# 2-MCU.net
KiCad netlist of a schematic drawn in Altium Designer
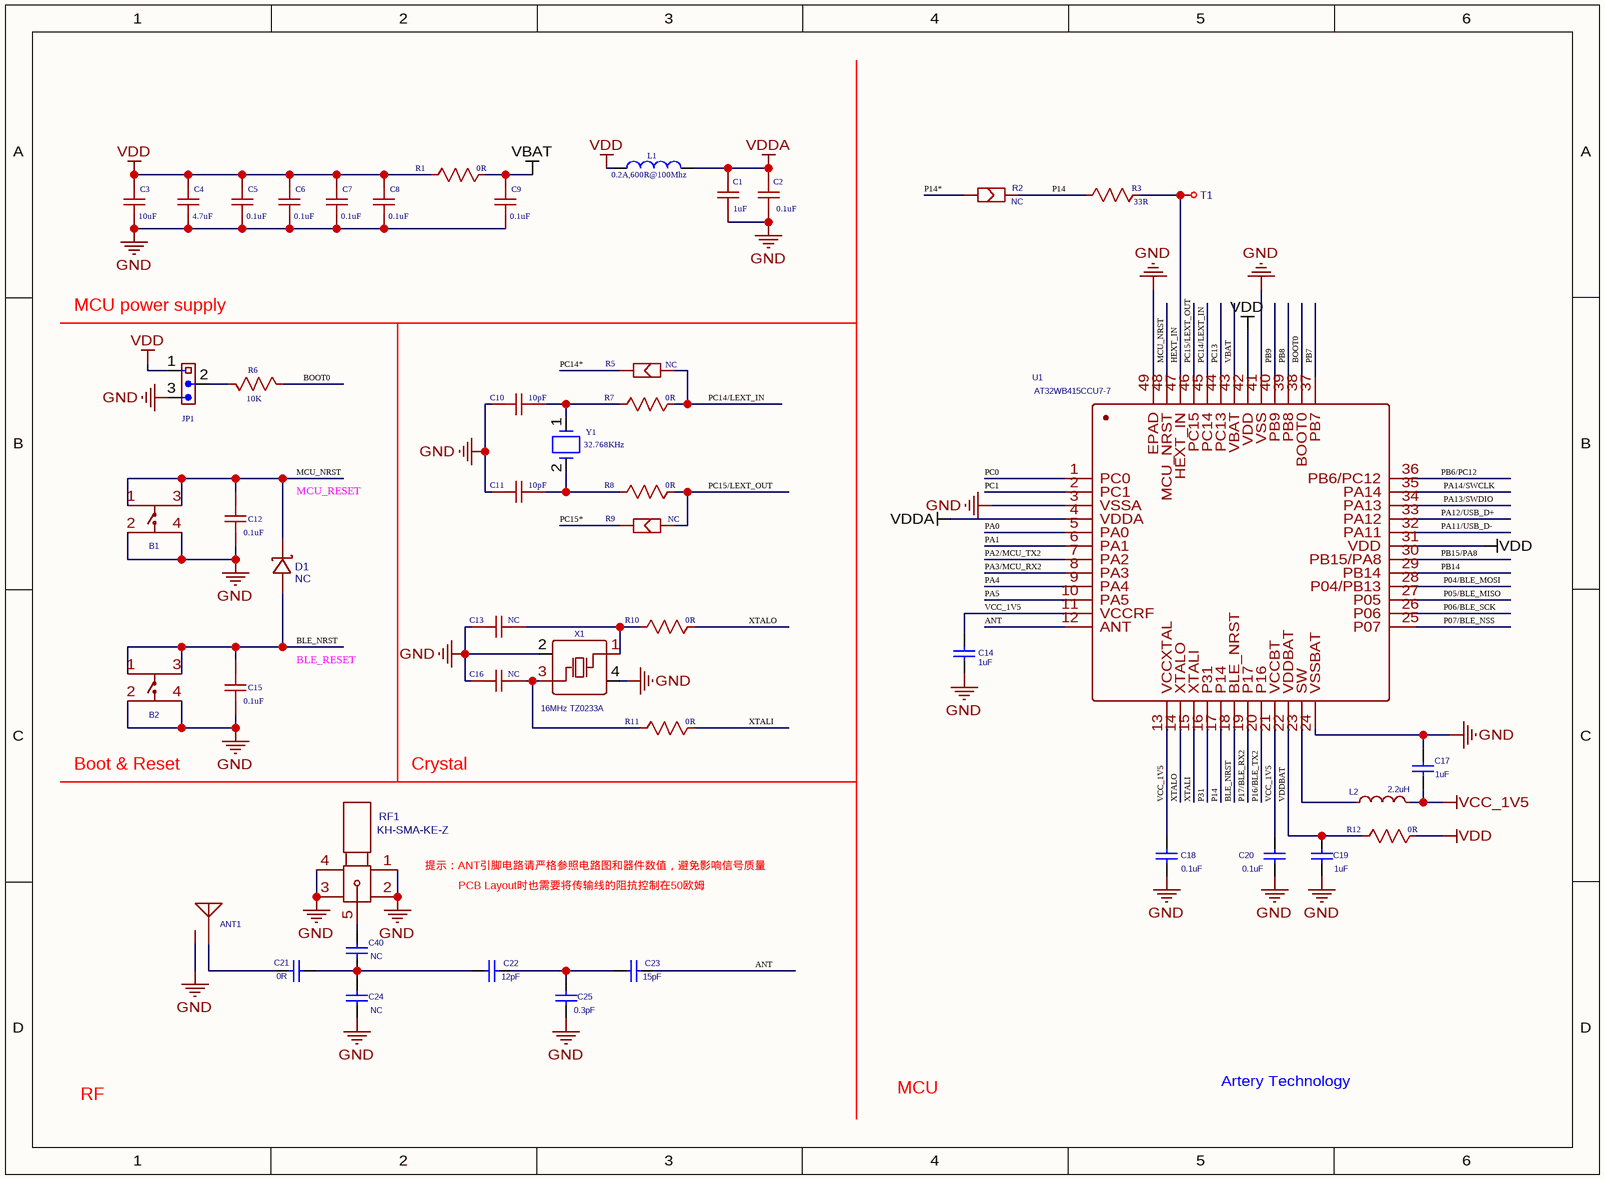
[diagram p0: 2-MCU.schdoc]

(export (version "E")
  (design (tool "Eeschema 10.0.6"))
  (components
    (comp (ref "ANT1")
      (value "AN2051-245")
      (fields (field (name "BOM_SUPPLIER PART") "C99727"))
      (libsource (lib "altium-import") (part "root_0_AN2051-245_"))
    )
    (comp (ref "B1")
      (value "贴片按键6*6*5 黑色")
      (fields
        (field (name "BOM_SUPPLIER PART") "C707347")
        (field (name "BOM_MANUFACTURER PART") "K2-1102SP-C3SC-04")
        (field (name "CONTRIBUTOR") "LCSC")
      )
      (libsource (lib "altium-import") (part "root_0_贴片按键6*6*5 黑色_"))
    )
    (comp (ref "B2")
      (value "贴片按键6*6*5 黑色")
      (fields
        (field (name "BOM_SUPPLIER PART") "C707347")
        (field (name "BOM_MANUFACTURER PART") "K2-1102SP-C3SC-04")
        (field (name "CONTRIBUTOR") "LCSC")
      )
      (libsource (lib "altium-import") (part "root_0_贴片按键6*6*5 黑色_"))
    )
    (comp (ref "C1")
      (value "1uF")
      (fields (field (name "CONTRIBUTOR") "LCEDA_Lib"))
      (libsource (lib "altium-import") (part "root_1_1uF_"))
    )
    (comp (ref "C2")
      (value "0.1uF")
      (fields (field (name "CONTRIBUTOR") "LCEDA_Lib"))
      (libsource (lib "altium-import") (part "root_1_0.1uF_"))
    )
    (comp (ref "C3")
      (value "10uF")
      (fields (field (name "CONTRIBUTOR") "LCEDA_Lib"))
      (libsource (lib "altium-import") (part "root_3_10uF_"))
    )
    (comp (ref "C4")
      (value "4.7uF")
      (fields (field (name "CONTRIBUTOR") "LCEDA_Lib"))
      (libsource (lib "altium-import") (part "root_3_4.7uF_"))
    )
    (comp (ref "C5")
      (value "0.1uF")
      (fields (field (name "CONTRIBUTOR") "LCEDA_Lib"))
      (libsource (lib "altium-import") (part "root_3_0.1uF_"))
    )
    (comp (ref "C6")
      (value "0.1uF")
      (fields (field (name "CONTRIBUTOR") "LCEDA_Lib"))
      (libsource (lib "altium-import") (part "root_3_0.1uF_"))
    )
    (comp (ref "C7")
      (value "0.1uF")
      (fields (field (name "CONTRIBUTOR") "LCEDA_Lib"))
      (libsource (lib "altium-import") (part "root_3_0.1uF_"))
    )
    (comp (ref "C8")
      (value "0.1uF")
      (fields (field (name "CONTRIBUTOR") "LCEDA_Lib"))
      (libsource (lib "altium-import") (part "root_3_0.1uF_"))
    )
    (comp (ref "C9")
      (value "0.1uF")
      (fields (field (name "CONTRIBUTOR") "LCEDA_Lib"))
      (libsource (lib "altium-import") (part "root_3_0.1uF_"))
    )
    (comp (ref "C10")
      (value "10pF")
      (fields (field (name "CONTRIBUTOR") "LCEDA_Lib"))
      (libsource (lib "altium-import") (part "root_0_10pF_"))
    )
    (comp (ref "C11")
      (value "10pF")
      (fields (field (name "CONTRIBUTOR") "LCEDA_Lib"))
      (libsource (lib "altium-import") (part "root_0_10pF_"))
    )
    (comp (ref "C12")
      (value "0.1uF")
      (fields (field (name "CONTRIBUTOR") "LCEDA_Lib"))
      (libsource (lib "altium-import") (part "root_1_0.1uF_"))
    )
    (comp (ref "C13")
      (value "NC")
      (fields (field (name "CONTRIBUTOR") "LCEDA_Lib"))
      (libsource (lib "altium-import") (part "root_0_NC_"))
    )
    (comp (ref "C14") (value "1uF") (libsource (lib "") (part "root_1_1uF__1")))
    (comp (ref "C15")
      (value "0.1uF")
      (fields (field (name "CONTRIBUTOR") "LCEDA_Lib"))
      (libsource (lib "altium-import") (part "root_1_0.1uF_"))
    )
    (comp (ref "C16")
      (value "NC")
      (fields (field (name "CONTRIBUTOR") "LCEDA_Lib"))
      (libsource (lib "altium-import") (part "root_0_NC_"))
    )
    (comp (ref "C17") (value "1uF") (libsource (lib "altium-import") (part "root_3_1uF_")))
    (comp (ref "C18") (value "0.1uF") (libsource (lib "") (part "root_3_0.1uF__1")))
    (comp (ref "C19") (value "1uF") (libsource (lib "altium-import") (part "root_3_1uF_")))
    (comp (ref "C20") (value "0.1uF") (libsource (lib "") (part "root_1_0.1uF__1")))
    (comp (ref "C21") (value "0R") (libsource (lib "altium-import") (part "root_0_0R_")))
    (comp (ref "C22") (value "12pF") (libsource (lib "altium-import") (part "root_2_12pF_")))
    (comp (ref "C23") (value "15pF") (libsource (lib "altium-import") (part "root_2_15pF_")))
    (comp (ref "C24") (value "NC") (libsource (lib "altium-import") (part "root_3_NC_")))
    (comp (ref "C25") (value "0.3pF") (libsource (lib "altium-import") (part "root_3_0.3pF_")))
    (comp (ref "C40") (value "NC") (libsource (lib "altium-import") (part "root_3_NC_")))
    (comp (ref "D1")
      (value "NC")
      (fields (field (name "BOM_MANUFACTURER PART") "B5819WS") (field (name "BOM_SUPPLIER PART") "C64886"))
      (libsource (lib "") (part "root_3_NC__1"))
    )
    (comp (ref "JP1") (value "Header 1x3") (libsource (lib "altium-import") (part "root_2_Header 1x3_")))
    (comp (ref "L1")
      (value "0.2A,600R@100Mhz")
      (fields (field (name "CONTRIBUTOR") "twb17"))
      (libsource (lib "altium-import") (part "root_0_0.2A,600R@100Mhz_"))
    )
    (comp (ref "L2")
      (value "2.2uH")
      (fields
        (field (name "BOM_MANUFACTURER PART") "MPH201210S2R2MT")
        (field (name "BOM_SUPPLIER PART") "C55755")
      )
      (libsource (lib "altium-import") (part "root_0_2.2uH_"))
    )
    (comp (ref "R1")
      (value "0R")
      (fields (field (name "CONTRIBUTOR") "LCEDA_Lib"))
      (libsource (lib "altium-import") (part "root_2_0R_"))
    )
    (comp (ref "R2")
      (value "NC")
      (fields (field (name "CONTRIBUTOR") "twb17"))
      (libsource (lib "") (part "root_0_NC__1"))
    )
    (comp (ref "R3")
      (value "33R")
      (fields (field (name "CONTRIBUTOR") "LCEDA_Lib"))
      (libsource (lib "altium-import") (part "root_2_33R_"))
    )
    (comp (ref "R5")
      (value "NC")
      (fields (field (name "CONTRIBUTOR") "twb17"))
      (libsource (lib "altium-import") (part "root_2_NC_"))
    )
    (comp (ref "R6")
      (value "10K")
      (fields (field (name "CONTRIBUTOR") "LCEDA_Lib"))
      (libsource (lib "altium-import") (part "root_0_10K_"))
    )
    (comp (ref "R7")
      (value "0R")
      (fields (field (name "CONTRIBUTOR") "LCEDA_Lib"))
      (libsource (lib "altium-import") (part "root_2_0R_"))
    )
    (comp (ref "R8")
      (value "0R")
      (fields (field (name "CONTRIBUTOR") "LCEDA_Lib"))
      (libsource (lib "altium-import") (part "root_2_0R_"))
    )
    (comp (ref "R9")
      (value "NC")
      (fields (field (name "CONTRIBUTOR") "twb17"))
      (libsource (lib "altium-import") (part "root_2_NC_"))
    )
    (comp (ref "R10")
      (value "0R")
      (fields (field (name "CONTRIBUTOR") "LCEDA_Lib"))
      (libsource (lib "altium-import") (part "root_2_0R_"))
    )
    (comp (ref "R11")
      (value "0R")
      (fields (field (name "CONTRIBUTOR") "LCEDA_Lib"))
      (libsource (lib "altium-import") (part "root_2_0R_"))
    )
    (comp (ref "R12")
      (value "0R")
      (fields (field (name "CONTRIBUTOR") "LCEDA_Lib"))
      (libsource (lib "altium-import") (part "root_2_0R_"))
    )
    (comp (ref "RF1")
      (value "KH-SMA-KE-Z")
      (fields (field (name "BOM_SUPPLIER PART") "C504007") (field (name "CONTRIBUTOR") "LCSC"))
      (libsource (lib "altium-import") (part "root_3_KH-SMA-KE-Z_"))
    )
    (comp (ref "T1")
      (value "Testpoint1")
      (fields (field (name "CONTRIBUTOR") "twb17"))
      (libsource (lib "altium-import") (part "root_2_Testpoint1_"))
    )
    (comp (ref "U1")
      (value "AT32WB415CCU7-7")
      (fields (field (name "CONTRIBUTOR") "twb17"))
      (libsource (lib "altium-import") (part "root_0_AT32WB415CCU7-7_"))
    )
    (comp (ref "X1")
      (value "16MHz TZ0233A")
      (fields
        (field (name "BOM_SUPPLIER PART") "C112586")
        (field (name "BOM_MANUFACTURER PART") "X503216MSB4SI")
        (field (name "CONTRIBUTOR") "LCSC")
      )
      (libsource (lib "altium-import") (part "root_2_16MHz TZ0233A_"))
    )
    (comp (ref "Y1")
      (value "32.768KHz")
      (fields (field (name "CONTRIBUTOR") "twb17"))
      (libsource (lib "altium-import") (part "root_1_32.768KHz_"))
    )
  )
  (nets
    (net (code "1") (name "/ANT") (class "Default")
      (node (ref "C23") (pin "1") (pinfunction "1_1") (pintype "passive"))
      (node (ref "U1") (pin "12") (pinfunction "ANT_12") (pintype "passive"))
    )
    (net (code "2") (name "/BLE_NRST") (class "Default")
      (node (ref "B2") (pin "1") (pinfunction "1_1") (pintype "passive"))
      (node (ref "B2") (pin "3") (pinfunction "3_3") (pintype "passive"))
      (node (ref "C15") (pin "2") (pinfunction "2_2") (pintype "passive"))
      (node (ref "D1") (pin "2") (pinfunction "A_2") (pintype "passive"))
      (node (ref "U1") (pin "18") (pinfunction "BLE_NRST_18") (pintype "passive"))
    )
    (net (code "3") (name "/BOOT0") (class "Default")
      (node (ref "R6") (pin "2") (pinfunction "2_2") (pintype "passive"))
      (node (ref "U1") (pin "38") (pinfunction "BOOT0_38") (pintype "passive"))
    )
    (net (code "4") (name "/HEXT_IN") (class "Default")
      (node (ref "R3") (pin "1") (pinfunction "1_1") (pintype "passive"))
      (node (ref "T1") (pin "1") (pinfunction "1_1") (pintype "passive"))
      (node (ref "U1") (pin "47") (pinfunction "HEXT_IN_47") (pintype "passive"))
    )
    (net (code "5") (name "/MCU_NRST") (class "Default")
      (node (ref "B1") (pin "1") (pinfunction "1_1") (pintype "passive"))
      (node (ref "B1") (pin "3") (pinfunction "3_3") (pintype "passive"))
      (node (ref "C12") (pin "2") (pinfunction "2_2") (pintype "passive"))
      (node (ref "D1") (pin "1") (pinfunction "K_1") (pintype "passive"))
      (node (ref "U1") (pin "48") (pinfunction "MCU_NRST_48") (pintype "passive"))
    )
    (net (code "6") (name "/P04{slash}BLE_MOSI") (class "Default")
      (node (ref "U1") (pin "28") (pinfunction "P04/PB13_28") (pintype "passive"))
    )
    (net (code "7") (name "/P05{slash}BLE_MISO") (class "Default")
      (node (ref "U1") (pin "27") (pinfunction "P05_27") (pintype "passive"))
    )
    (net (code "8") (name "/P06{slash}BLE_SCK") (class "Default")
      (node (ref "U1") (pin "26") (pinfunction "P06_26") (pintype "passive"))
    )
    (net (code "9") (name "/P07{slash}BLE_NSS") (class "Default")
      (node (ref "U1") (pin "25") (pinfunction "P07_25") (pintype "passive"))
    )
    (net (code "10") (name "/P14") (class "Default")
      (node (ref "R2") (pin "2") (pinfunction "2_2") (pintype "passive"))
      (node (ref "R3") (pin "2") (pinfunction "2_2") (pintype "passive"))
      (node (ref "U1") (pin "17") (pinfunction "P14_17") (pintype "passive"))
    )
    (net (code "11") (name "/P14*") (class "Default")
      (node (ref "R2") (pin "1") (pinfunction "1_1") (pintype "passive"))
    )
    (net (code "12") (name "/P16{slash}BLE_TX2") (class "Default")
      (node (ref "U1") (pin "20") (pinfunction "P16_20") (pintype "passive"))
    )
    (net (code "13") (name "/P17{slash}BLE_RX2") (class "Default")
      (node (ref "U1") (pin "19") (pinfunction "P17_19") (pintype "passive"))
    )
    (net (code "14") (name "/P31") (class "Default")
      (node (ref "U1") (pin "16") (pinfunction "P31_16") (pintype "passive"))
    )
    (net (code "15") (name "/PA0") (class "Default")
      (node (ref "U1") (pin "5") (pinfunction "PA0_5") (pintype "passive"))
    )
    (net (code "16") (name "/PA1") (class "Default")
      (node (ref "U1") (pin "6") (pinfunction "PA1_6") (pintype "passive"))
    )
    (net (code "17") (name "/PA2{slash}MCU_TX2") (class "Default")
      (node (ref "U1") (pin "7") (pinfunction "PA2_7") (pintype "passive"))
    )
    (net (code "18") (name "/PA3{slash}MCU_RX2") (class "Default")
      (node (ref "U1") (pin "8") (pinfunction "PA3_8") (pintype "passive"))
    )
    (net (code "19") (name "/PA4") (class "Default")
      (node (ref "U1") (pin "9") (pinfunction "PA4_9") (pintype "passive"))
    )
    (net (code "20") (name "/PA5") (class "Default")
      (node (ref "U1") (pin "10") (pinfunction "PA5_10") (pintype "passive"))
    )
    (net (code "21") (name "/PA11{slash}USB_D-") (class "Default")
      (node (ref "U1") (pin "32") (pinfunction "PA11_32") (pintype "passive"))
    )
    (net (code "22") (name "/PA12{slash}USB_D+") (class "Default")
      (node (ref "U1") (pin "33") (pinfunction "PA12_33") (pintype "passive"))
    )
    (net (code "23") (name "/PA13{slash}SWDIO") (class "Default")
      (node (ref "U1") (pin "34") (pinfunction "PA13_34") (pintype "passive"))
    )
    (net (code "24") (name "/PA14{slash}SWCLK") (class "Default")
      (node (ref "U1") (pin "35") (pinfunction "PA14_35") (pintype "passive"))
    )
    (net (code "25") (name "/PB6{slash}PC12") (class "Default")
      (node (ref "U1") (pin "36") (pinfunction "PB6/PC12_36") (pintype "passive"))
    )
    (net (code "26") (name "/PB7") (class "Default")
      (node (ref "U1") (pin "37") (pinfunction "PB7_37") (pintype "passive"))
    )
    (net (code "27") (name "/PB8") (class "Default")
      (node (ref "U1") (pin "39") (pinfunction "PB8_39") (pintype "passive"))
    )
    (net (code "28") (name "/PB9") (class "Default")
      (node (ref "U1") (pin "40") (pinfunction "PB9_40") (pintype "passive"))
    )
    (net (code "29") (name "/PB14") (class "Default")
      (node (ref "U1") (pin "29") (pinfunction "PB14_29") (pintype "passive"))
    )
    (net (code "30") (name "/PB15{slash}PA8") (class "Default")
      (node (ref "U1") (pin "30") (pinfunction "PB15/PA8_30") (pintype "passive"))
    )
    (net (code "31") (name "/PC0") (class "Default")
      (node (ref "U1") (pin "1") (pinfunction "PC0_1") (pintype "passive"))
    )
    (net (code "32") (name "/PC1") (class "Default")
      (node (ref "U1") (pin "2") (pinfunction "PC1_2") (pintype "passive"))
    )
    (net (code "33") (name "/PC13") (class "Default")
      (node (ref "U1") (pin "44") (pinfunction "PC13_44") (pintype "passive"))
    )
    (net (code "34") (name "/PC14*") (class "Default")
      (node (ref "R5") (pin "2") (pinfunction "2_2") (pintype "passive"))
    )
    (net (code "35") (name "/PC14{slash}LEXT_IN") (class "Default")
      (node (ref "R5") (pin "1") (pinfunction "1_1") (pintype "passive"))
      (node (ref "R7") (pin "1") (pinfunction "1_1") (pintype "passive"))
      (node (ref "U1") (pin "45") (pinfunction "PC14_45") (pintype "passive"))
    )
    (net (code "36") (name "/PC15*") (class "Default")
      (node (ref "R9") (pin "2") (pinfunction "2_2") (pintype "passive"))
    )
    (net (code "37") (name "/PC15{slash}LEXT_OUT") (class "Default")
      (node (ref "R8") (pin "1") (pinfunction "1_1") (pintype "passive"))
      (node (ref "R9") (pin "1") (pinfunction "1_1") (pintype "passive"))
      (node (ref "U1") (pin "46") (pinfunction "PC15_46") (pintype "passive"))
    )
    (net (code "38") (name "/VDDBAT") (class "Default")
      (node (ref "C19") (pin "1") (pinfunction "1_1") (pintype "passive"))
      (node (ref "R12") (pin "2") (pinfunction "2_2") (pintype "passive"))
      (node (ref "U1") (pin "22") (pinfunction "VDDBAT_22") (pintype "passive"))
    )
    (net (code "39") (name "/XTALI") (class "Default")
      (node (ref "R11") (pin "1") (pinfunction "1_1") (pintype "passive"))
      (node (ref "U1") (pin "15") (pinfunction "XTALI_15") (pintype "passive"))
    )
    (net (code "40") (name "/XTALO") (class "Default")
      (node (ref "R10") (pin "1") (pinfunction "1_1") (pintype "passive"))
      (node (ref "U1") (pin "14") (pinfunction "XTALO_14") (pintype "passive"))
    )
    (net (code "41") (name "GND") (class "Default")
      (node (ref "ANT1") (pin "2") (pinfunction "2_2") (pintype "passive"))
      (node (ref "B1") (pin "2") (pinfunction "2_2") (pintype "passive"))
      (node (ref "B1") (pin "4") (pinfunction "4_4") (pintype "passive"))
      (node (ref "B2") (pin "2") (pinfunction "2_2") (pintype "passive"))
      (node (ref "B2") (pin "4") (pinfunction "4_4") (pintype "passive"))
      (node (ref "C1") (pin "1") (pinfunction "1_1") (pintype "passive"))
      (node (ref "C10") (pin "1") (pinfunction "1_1") (pintype "passive"))
      (node (ref "C11") (pin "1") (pinfunction "1_1") (pintype "passive"))
      (node (ref "C12") (pin "1") (pinfunction "1_1") (pintype "passive"))
      (node (ref "C13") (pin "1") (pinfunction "1_1") (pintype "passive"))
      (node (ref "C14") (pin "1") (pinfunction "1_1") (pintype "passive"))
      (node (ref "C15") (pin "1") (pinfunction "1_1") (pintype "passive"))
      (node (ref "C16") (pin "1") (pinfunction "1_1") (pintype "passive"))
      (node (ref "C17") (pin "1") (pinfunction "1_1") (pintype "passive"))
      (node (ref "C18") (pin "2") (pinfunction "2_2") (pintype "passive"))
      (node (ref "C19") (pin "2") (pinfunction "2_2") (pintype "passive"))
      (node (ref "C2") (pin "1") (pinfunction "1_1") (pintype "passive"))
      (node (ref "C20") (pin "1") (pinfunction "1_1") (pintype "passive"))
      (node (ref "C24") (pin "2") (pinfunction "2_2") (pintype "passive"))
      (node (ref "C25") (pin "2") (pinfunction "2_2") (pintype "passive"))
      (node (ref "C3") (pin "2") (pinfunction "2_2") (pintype "passive"))
      (node (ref "C4") (pin "2") (pinfunction "2_2") (pintype "passive"))
      (node (ref "C5") (pin "2") (pinfunction "2_2") (pintype "passive"))
      (node (ref "C6") (pin "2") (pinfunction "2_2") (pintype "passive"))
      (node (ref "C7") (pin "2") (pinfunction "2_2") (pintype "passive"))
      (node (ref "C8") (pin "2") (pinfunction "2_2") (pintype "passive"))
      (node (ref "C9") (pin "2") (pinfunction "2_2") (pintype "passive"))
      (node (ref "JP1") (pin "3") (pinfunction "3_3") (pintype "passive"))
      (node (ref "RF1") (pin "1") (pinfunction "1_1") (pintype "passive"))
      (node (ref "RF1") (pin "2") (pinfunction "2_2") (pintype "passive"))
      (node (ref "RF1") (pin "3") (pinfunction "3_3") (pintype "passive"))
      (node (ref "RF1") (pin "4") (pinfunction "4_4") (pintype "passive"))
      (node (ref "U1") (pin "24") (pinfunction "VSSBAT_24") (pintype "passive"))
      (node (ref "U1") (pin "3") (pinfunction "VSSA_3") (pintype "passive"))
      (node (ref "U1") (pin "41") (pinfunction "VSS_41") (pintype "passive"))
      (node (ref "U1") (pin "49") (pinfunction "EPAD_49") (pintype "passive"))
      (node (ref "X1") (pin "2") (pinfunction "GND_2") (pintype "passive"))
      (node (ref "X1") (pin "4") (pinfunction "GND_4") (pintype "passive"))
    )
    (net (code "42") (name "Net-(ANT1-ANT)") (class "Default")
      (node (ref "ANT1") (pin "1") (pinfunction "ANT_1") (pintype "passive"))
      (node (ref "C21") (pin "1") (pinfunction "1_1") (pintype "passive"))
    )
    (net (code "43") (name "Net-(C10-Pad2)") (class "Default")
      (node (ref "C10") (pin "2") (pinfunction "2_2") (pintype "passive"))
      (node (ref "R7") (pin "2") (pinfunction "2_2") (pintype "passive"))
      (node (ref "Y1") (pin "1") (pinfunction "1_1") (pintype "passive"))
    )
    (net (code "44") (name "Net-(C11-Pad2)") (class "Default")
      (node (ref "C11") (pin "2") (pinfunction "2_2") (pintype "passive"))
      (node (ref "R8") (pin "2") (pinfunction "2_2") (pintype "passive"))
      (node (ref "Y1") (pin "2") (pinfunction "2_2") (pintype "passive"))
    )
    (net (code "45") (name "Net-(C21-Pad2)") (class "Default")
      (node (ref "C21") (pin "2") (pinfunction "2_2") (pintype "passive"))
      (node (ref "C22") (pin "2") (pinfunction "2_2") (pintype "passive"))
      (node (ref "C24") (pin "1") (pinfunction "1_1") (pintype "passive"))
      (node (ref "C40") (pin "2") (pinfunction "2_2") (pintype "passive"))
    )
    (net (code "46") (name "Net-(C22-Pad1)") (class "Default")
      (node (ref "C22") (pin "1") (pinfunction "1_1") (pintype "passive"))
      (node (ref "C23") (pin "2") (pinfunction "2_2") (pintype "passive"))
      (node (ref "C25") (pin "1") (pinfunction "1_1") (pintype "passive"))
    )
    (net (code "47") (name "Net-(C40-Pad1)") (class "Default")
      (node (ref "C40") (pin "1") (pinfunction "1_1") (pintype "passive"))
      (node (ref "RF1") (pin "5") (pinfunction "5_5") (pintype "passive"))
    )
    (net (code "48") (name "Net-(JP1-Pad2)") (class "Default")
      (node (ref "JP1") (pin "2") (pinfunction "2_2") (pintype "passive"))
      (node (ref "R6") (pin "1") (pinfunction "1_1") (pintype "passive"))
    )
    (net (code "49") (name "Net-(U1-SW)") (class "Default")
      (node (ref "L2") (pin "1") (pinfunction "1_1") (pintype "passive"))
      (node (ref "U1") (pin "23") (pinfunction "SW_23") (pintype "passive"))
    )
    (net (code "50") (name "Net-(X1-OSC1)") (class "Default")
      (node (ref "C13") (pin "2") (pinfunction "2_2") (pintype "passive"))
      (node (ref "R10") (pin "2") (pinfunction "2_2") (pintype "passive"))
      (node (ref "X1") (pin "1") (pinfunction "OSC1_1") (pintype "passive"))
    )
    (net (code "51") (name "Net-(X1-OSC2)") (class "Default")
      (node (ref "C16") (pin "2") (pinfunction "2_2") (pintype "passive"))
      (node (ref "R11") (pin "2") (pinfunction "2_2") (pintype "passive"))
      (node (ref "X1") (pin "3") (pinfunction "OSC2_3") (pintype "passive"))
    )
    (net (code "52") (name "VBAT") (class "Default")
      (node (ref "C9") (pin "1") (pinfunction "1_1") (pintype "passive"))
      (node (ref "R1") (pin "1") (pinfunction "1_1") (pintype "passive"))
      (node (ref "U1") (pin "43") (pinfunction "VBAT_43") (pintype "passive"))
    )
    (net (code "53") (name "VCC_1V5") (class "Default")
      (node (ref "C14") (pin "2") (pinfunction "2_2") (pintype "passive"))
      (node (ref "C17") (pin "2") (pinfunction "2_2") (pintype "passive"))
      (node (ref "C18") (pin "1") (pinfunction "1_1") (pintype "passive"))
      (node (ref "C20") (pin "2") (pinfunction "2_2") (pintype "passive"))
      (node (ref "L2") (pin "2") (pinfunction "2_2") (pintype "passive"))
      (node (ref "U1") (pin "11") (pinfunction "VCCRF_11") (pintype "passive"))
      (node (ref "U1") (pin "13") (pinfunction "VCCXTAL_13") (pintype "passive"))
      (node (ref "U1") (pin "21") (pinfunction "VCCBT_21") (pintype "passive"))
    )
    (net (code "54") (name "VDD") (class "Default")
      (node (ref "C3") (pin "1") (pinfunction "1_1") (pintype "passive"))
      (node (ref "C4") (pin "1") (pinfunction "1_1") (pintype "passive"))
      (node (ref "C5") (pin "1") (pinfunction "1_1") (pintype "passive"))
      (node (ref "C6") (pin "1") (pinfunction "1_1") (pintype "passive"))
      (node (ref "C7") (pin "1") (pinfunction "1_1") (pintype "passive"))
      (node (ref "C8") (pin "1") (pinfunction "1_1") (pintype "passive"))
      (node (ref "JP1") (pin "1") (pinfunction "1_1") (pintype "passive"))
      (node (ref "L1") (pin "1") (pinfunction "1_1") (pintype "passive"))
      (node (ref "R1") (pin "2") (pinfunction "2_2") (pintype "passive"))
      (node (ref "R12") (pin "1") (pinfunction "1_1") (pintype "passive"))
      (node (ref "U1") (pin "31") (pinfunction "VDD_31") (pintype "passive"))
      (node (ref "U1") (pin "42") (pinfunction "VDD_42") (pintype "passive"))
    )
    (net (code "55") (name "VDDA") (class "Default")
      (node (ref "C1") (pin "2") (pinfunction "2_2") (pintype "passive"))
      (node (ref "C2") (pin "2") (pinfunction "2_2") (pintype "passive"))
      (node (ref "L1") (pin "2") (pinfunction "2_2") (pintype "passive"))
      (node (ref "U1") (pin "4") (pinfunction "VDDA_4") (pintype "passive"))
    )
  )
)
